# Shining_Pig.net
KiCad netlist of a schematic drawn in Altium Designer
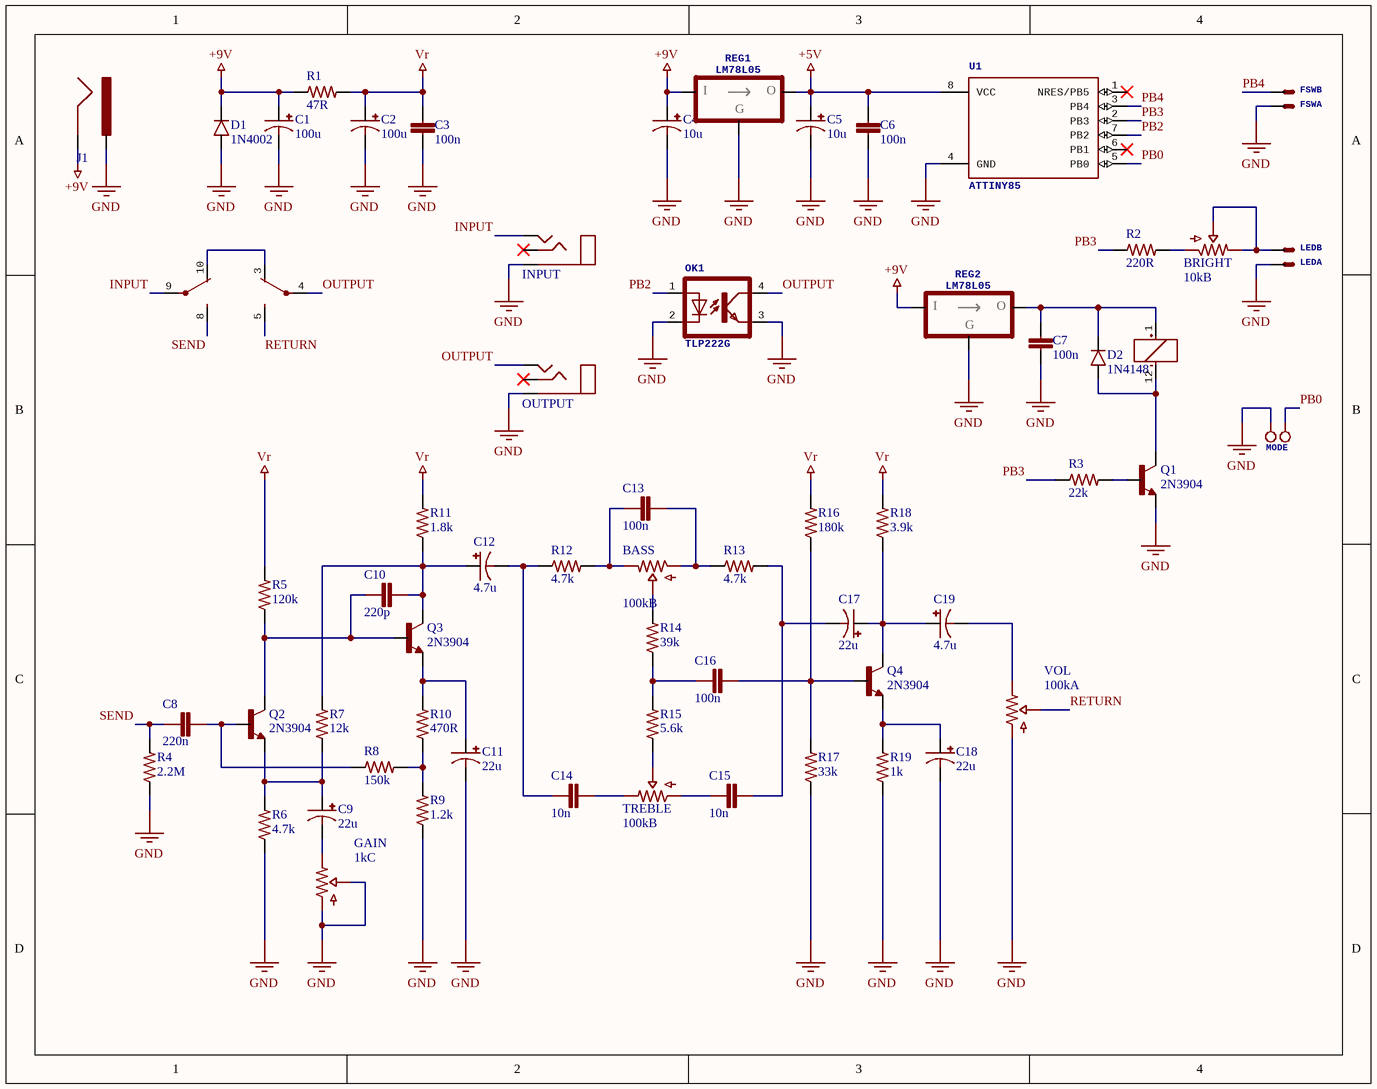
[diagram p0: Shining Pig.SchDoc]

(export (version "E")
  (design (tool "Eeschema 10.0.6"))
  (components
    (comp (ref "BASS")
      (value "100kB")
      (footprint "ALPHA_16mm_BOTTOM")
      (description "100k Lin potentiometer round shaft")
      (libsource (lib "Pedals") (part "POT_100kB_ALPHA_16mm"))
    )
    (comp (ref "BRIGHT")
      (value "10kB")
      (footprint "BOURNS_3362P")
      (description "10k Lin 3362P trimmer")
      (libsource (lib "Pedals") (part "TRIM_10kB_3362P"))
    )
    (comp (ref "C1")
      (value "100u")
      (footprint "ELEC_063_025")
      (description "100u 25V electrolytic capacitor")
      (libsource (lib "Pedals") (part "C_ELEC_100u_25V"))
    )
    (comp (ref "C2")
      (value "100u")
      (footprint "ELEC_063_025")
      (description "100u 25V electrolytic capacitor")
      (libsource (lib "Pedals") (part "C_ELEC_100u_25V"))
    )
    (comp (ref "C3")
      (value "100n")
      (footprint "CER_050")
      (description "100n MLCC X7R radial capacitor")
      (libsource (lib "Pedals") (part "C_CER_100n"))
    )
    (comp (ref "C4")
      (value "10u")
      (footprint "ELEC_040_020")
      (description "10u 50V electrolytic capacitor")
      (libsource (lib "Pedals") (part "C_ELEC_10u_50V"))
    )
    (comp (ref "C5")
      (value "10u")
      (footprint "ELEC_040_020")
      (description "10u 50V electrolytic capacitor")
      (libsource (lib "Pedals") (part "C_ELEC_10u_50V"))
    )
    (comp (ref "C6")
      (value "100n")
      (footprint "CER_050")
      (description "100n MLCC X7R radial capacitor")
      (libsource (lib "") (part "C_CER_100n_1"))
    )
    (comp (ref "C7")
      (value "100n")
      (footprint "CER_050")
      (description "100n MLCC X7R radial capacitor")
      (libsource (lib "Pedals") (part "C_CER_100n"))
    )
    (comp (ref "C8")
      (value "220n")
      (footprint "FILMBOX_SMALL")
      (description "220n 100V polyester film box capacitor")
      (libsource (lib "Pedals") (part "C_FILMBOX_220n"))
    )
    (comp (ref "C9")
      (value "22u")
      (footprint "ELEC_LESR_050_020")
      (description "22u 50V Low ESR ectrolytic capacitor")
      (libsource (lib "Pedals") (part "C_ELEC_LESR_22u_50V"))
    )
    (comp (ref "C10")
      (value "220p")
      (footprint "CER_050")
      (description "220p MLCC X7R radial capacitor")
      (libsource (lib "Pedals") (part "C_CER_220p"))
    )
    (comp (ref "C11")
      (value "22u")
      (footprint "ELEC_LESR_050_020")
      (description "22u 50V Low ESR ectrolytic capacitor")
      (libsource (lib "Pedals") (part "C_ELEC_LESR_22u_50V"))
    )
    (comp (ref "C12")
      (value "4.7u")
      (footprint "ELEC_LESR_050_020")
      (description "4.7u 50V Low ESR ectrolytic capacitor")
      (libsource (lib "Pedals") (part "C_ELEC_LESR_4.7u_50V"))
    )
    (comp (ref "C13")
      (value "100n")
      (footprint "FILMBOX_SMALL")
      (description "100n 100V polyester film box capacitor")
      (libsource (lib "Pedals") (part "C_FILMBOX_100n"))
    )
    (comp (ref "C14")
      (value "10n")
      (footprint "FILMBOX_SMALL")
      (description "10n 100V polyester film box capacitor")
      (libsource (lib "Pedals") (part "C_FILMBOX_10n"))
    )
    (comp (ref "C15")
      (value "10n")
      (footprint "FILMBOX_SMALL")
      (description "10n 100V polyester film box capacitor")
      (libsource (lib "Pedals") (part "C_FILMBOX_10n"))
    )
    (comp (ref "C16")
      (value "100n")
      (footprint "FILMBOX_SMALL")
      (description "100n 100V polyester film box capacitor")
      (libsource (lib "Pedals") (part "C_FILMBOX_100n"))
    )
    (comp (ref "C17")
      (value "22u")
      (footprint "ELEC_LESR_050_020")
      (description "22u 50V Low ESR ectrolytic capacitor")
      (libsource (lib "") (part "C_ELEC_LESR_22u_50V_1"))
    )
    (comp (ref "C18")
      (value "22u")
      (footprint "ELEC_LESR_050_020")
      (description "22u 50V Low ESR ectrolytic capacitor")
      (libsource (lib "Pedals") (part "C_ELEC_LESR_22u_50V"))
    )
    (comp (ref "C19")
      (value "4.7u")
      (footprint "ELEC_LESR_050_020")
      (description "4.7u 50V Low ESR ectrolytic capacitor")
      (libsource (lib "Pedals") (part "C_ELEC_LESR_4.7u_50V"))
    )
    (comp (ref "D1") (value "1N4002") (footprint "DO41_2") (libsource (lib "Pedals") (part "D_1N4002")))
    (comp (ref "D2") (value "1N4148") (footprint "DO35_2") (libsource (lib "Pedals") (part "D_1N4148")))
    (comp (ref "FSW")
      (value "J_JST-XH-02")
      (footprint "JST-XH-02")
      (description "2 Pins male XH header")
      (libsource (lib "Pedals") (part "J_JST-XH-02"))
    )
    (comp (ref "GAIN")
      (value "1kC")
      (footprint "ALPHA_16mm_BOTTOM")
      (description "1k Reverse log potentiometer round shaft")
      (libsource (lib "Pedals") (part "POT_1kC_ALPHA_16mm"))
    )
    (comp (ref "INPUT")
      (value "J_STEREO")
      (footprint "STEREO")
      (description "6.35mm stereo insulated socket jack PCB mounted")
      (libsource (lib "Pedals") (part "J_STEREO"))
    )
    (comp (ref "J1")
      (value "J_DC_JACK")
      (footprint "DC_JACK")
      (description "DC Power jack 2.1mm barrel")
      (libsource (lib "Pedals") (part "J_DC_JACK"))
    )
    (comp (ref "K1") (value "NA5W-K") (footprint "NA5") (libsource (lib "") (part "K_NA5W-K_2")))
    (comp (ref "LED")
      (value "J_JST-XH-02")
      (footprint "JST-XH-02")
      (description "2 Pins male XH header")
      (libsource (lib "Pedals") (part "J_JST-XH-02"))
    )
    (comp (ref "MODE")
      (value "J_HEADER_2PINS")
      (footprint "HEADER_2PINS")
      (description "2 Pins male header")
      (libsource (lib "Pedals") (part "J_HEADER_2PINS"))
    )
    (comp (ref "OK1") (value "TLP222G") (footprint "DIL4") (libsource (lib "Pedals") (part "OK_TLP222G")))
    (comp (ref "OUTPUT")
      (value "J_STEREO")
      (footprint "STEREO")
      (description "6.35mm stereo insulated socket jack PCB mounted")
      (libsource (lib "Pedals") (part "J_STEREO"))
    )
    (comp (ref "Q1") (value "2N3904") (footprint "TO92") (libsource (lib "Pedals") (part "Q_2N3904")))
    (comp (ref "Q2") (value "2N3904") (footprint "TO92") (libsource (lib "Pedals") (part "Q_2N3904")))
    (comp (ref "Q3") (value "2N3904") (footprint "TO92") (libsource (lib "Pedals") (part "Q_2N3904")))
    (comp (ref "Q4") (value "2N3904") (footprint "TO92") (libsource (lib "Pedals") (part "Q_2N3904")))
    (comp (ref "R1")
      (value "47R")
      (footprint "R_3_47R_025W")
      (description "47R metal film 1/4W Resistor")
      (libsource (lib "Pedals") (part "R_3_47R_025W"))
    )
    (comp (ref "R2")
      (value "220R")
      (footprint "R_3_220R_025W")
      (description "220R metal film 1/4W Resistor")
      (libsource (lib "Pedals") (part "R_3_220R_025W"))
    )
    (comp (ref "R3")
      (value "22k")
      (footprint "R_3_22k_025W")
      (description "22k metal film 1/4W Resistor")
      (libsource (lib "Pedals") (part "R_3_22k_025W"))
    )
    (comp (ref "R4")
      (value "2.2M")
      (footprint "R_3_2,2M_025W")
      (description "2.2M metal film 1/4W Resistor")
      (libsource (lib "Pedals") (part "R_3_2.2M_025W"))
    )
    (comp (ref "R5")
      (value "120k")
      (footprint "R_3_120k_025W")
      (description "120k metal film 1/4W Resistor")
      (libsource (lib "Pedals") (part "R_3_120k_025W"))
    )
    (comp (ref "R6")
      (value "4.7k")
      (footprint "R_3_4.7k_025W")
      (description "4.7kk metal film 1/4W Resistor")
      (libsource (lib "Pedals") (part "R_3_4.7k_025W"))
    )
    (comp (ref "R7")
      (value "12k")
      (footprint "R_3_12k_025W")
      (description "12k metal film 1/4W Resistor")
      (libsource (lib "Pedals") (part "R_3_12k_025W"))
    )
    (comp (ref "R8")
      (value "150k")
      (footprint "R_3_150k_025W")
      (description "150k metal film 1/4W Resistor")
      (libsource (lib "Pedals") (part "R_3_150k_025W"))
    )
    (comp (ref "R9")
      (value "1.2k")
      (footprint "R_3_1.2k_025W")
      (description "1.2k metal film 1/4W Resistor")
      (libsource (lib "Pedals") (part "R_3_1.2k_025W"))
    )
    (comp (ref "R10")
      (value "470R")
      (footprint "R_3_470R_025W")
      (description "470R metal film 1/4W Resistor")
      (libsource (lib "Pedals") (part "R_3_470R_025W"))
    )
    (comp (ref "R11")
      (value "1.8k")
      (footprint "R_3_1.8k_025W")
      (description "1.8k metal film 1/4W Resistor")
      (libsource (lib "Pedals") (part "R_3_1.8k_025W"))
    )
    (comp (ref "R12")
      (value "4.7k")
      (footprint "R_3_4.7k_025W")
      (description "4.7kk metal film 1/4W Resistor")
      (libsource (lib "Pedals") (part "R_3_4.7k_025W"))
    )
    (comp (ref "R13")
      (value "4.7k")
      (footprint "R_3_4.7k_025W")
      (description "4.7kk metal film 1/4W Resistor")
      (libsource (lib "Pedals") (part "R_3_4.7k_025W"))
    )
    (comp (ref "R14")
      (value "39k")
      (footprint "R_3_39k_025W")
      (description "39k metal film 1/4W Resistor")
      (libsource (lib "Pedals") (part "R_3_39k_025W"))
    )
    (comp (ref "R15")
      (value "5.6k")
      (footprint "R_3_5.6k_025W")
      (description "5.6k metal film 1/4W Resistor")
      (libsource (lib "Pedals") (part "R_3_5.6k_025W"))
    )
    (comp (ref "R16")
      (value "180k")
      (footprint "R_3_180k_025W")
      (description "180k metal film 1/4W Resistor")
      (libsource (lib "Pedals") (part "R_3_180k_025W"))
    )
    (comp (ref "R17")
      (value "33k")
      (footprint "R_3_33k_025W")
      (description "33k metal film 1/4W Resistor")
      (libsource (lib "Pedals") (part "R_3_33k_025W"))
    )
    (comp (ref "R18")
      (value "3.9k")
      (footprint "R_3_3.9k_025W")
      (description "3.9k metal film 1/4W Resistor")
      (libsource (lib "Pedals") (part "R_3_3.9k_025W"))
    )
    (comp (ref "R19")
      (value "1k")
      (footprint "R_3_1k_025W")
      (description "1k metal film 1/4W Resistor")
      (libsource (lib "Pedals") (part "R_3_1k_025W"))
    )
    (comp (ref "REG1")
      (value "LM78L05")
      (footprint "TO92")
      (description "78L05")
      (libsource (lib "Pedals") (part "REG_LM78L05"))
    )
    (comp (ref "REG2")
      (value "LM78L05")
      (footprint "TO92")
      (description "78L05")
      (libsource (lib "Pedals") (part "REG_LM78L05"))
    )
    (comp (ref "TREBLE")
      (value "100kB")
      (footprint "ALPHA_16mm_BOTTOM")
      (description "100k Lin potentiometer round shaft")
      (libsource (lib "Pedals") (part "POT_100kB_ALPHA_16mm"))
    )
    (comp (ref "U1")
      (value "ATTINY85")
      (footprint "DIP8")
      (description "ATTINY85-20PU")
      (libsource (lib "Pedals") (part "U_ATTINY85"))
    )
    (comp (ref "VOL")
      (value "100kA")
      (footprint "ALPHA_16mm_BOTTOM")
      (description "100k Log potentiometer round shaft")
      (libsource (lib "Pedals") (part "POT_100kA_ALPHA_16mm"))
    )
  )
  (nets
    (net (code "1") (name "+5V") (class "Default")
      (node (ref "C5") (pin "+") (pinfunction "+_+") (pintype "passive"))
      (node (ref "C6") (pin "2") (pinfunction "2_2") (pintype "passive"))
      (node (ref "REG1") (pin "3") (pinfunction "VO_3") (pintype "power_in"))
      (node (ref "U1") (pin "8") (pinfunction "VCC_8") (pintype "power_in"))
    )
    (net (code "2") (name "+9V") (class "Default")
      (node (ref "C1") (pin "+") (pinfunction "+_+") (pintype "passive"))
      (node (ref "C4") (pin "+") (pinfunction "+_+") (pintype "passive"))
      (node (ref "D1") (pin "C") (pinfunction "C_C") (pintype "passive"))
      (node (ref "J1") (pin "GND") (pinfunction "GND_GND") (pintype "passive"))
      (node (ref "R1") (pin "1") (pinfunction "1_1") (pintype "passive"))
      (node (ref "REG1") (pin "1") (pinfunction "VI_1") (pintype "power_in"))
      (node (ref "REG2") (pin "1") (pinfunction "VI_1") (pintype "power_in"))
    )
    (net (code "3") (name "/INPUT") (class "Default")
      (node (ref "INPUT") (pin "T") (pinfunction "T_T") (pintype "passive"))
      (node (ref "K1") (pin "9") (pinfunction "P_9") (pintype "passive"))
    )
    (net (code "4") (name "/OUTPUT") (class "Default")
      (node (ref "K1") (pin "4") (pinfunction "P_4") (pintype "passive"))
      (node (ref "OK1") (pin "4") (pinfunction "COL_4") (pintype "passive"))
      (node (ref "OUTPUT") (pin "T") (pinfunction "T_T") (pintype "passive"))
    )
    (net (code "5") (name "/PB0") (class "Default")
      (node (ref "MODE") (pin "2") (pinfunction "2_2") (pintype "passive"))
      (node (ref "U1") (pin "5") (pinfunction "PB0_5") (pintype "bidirectional"))
    )
    (net (code "6") (name "/PB2") (class "Default")
      (node (ref "OK1") (pin "1") (pinfunction "A_1") (pintype "passive"))
      (node (ref "U1") (pin "7") (pinfunction "PB2_7") (pintype "bidirectional"))
    )
    (net (code "7") (name "/PB3") (class "Default")
      (node (ref "R2") (pin "1") (pinfunction "1_1") (pintype "passive"))
      (node (ref "R3") (pin "1") (pinfunction "1_1") (pintype "passive"))
      (node (ref "U1") (pin "2") (pinfunction "PB3_2") (pintype "bidirectional"))
    )
    (net (code "8") (name "/PB4") (class "Default")
      (node (ref "FSW") (pin "1") (pinfunction "S_1") (pintype "passive"))
      (node (ref "U1") (pin "3") (pinfunction "PB4_3") (pintype "bidirectional"))
    )
    (net (code "9") (name "/RETURN") (class "Default")
      (node (ref "K1") (pin "5") (pinfunction "S_5") (pintype "passive"))
      (node (ref "VOL") (pin "2") (pinfunction "2_2") (pintype "passive"))
    )
    (net (code "10") (name "/SEND") (class "Default")
      (node (ref "C8") (pin "2") (pinfunction "2_2") (pintype "passive"))
      (node (ref "K1") (pin "8") (pinfunction "S_8") (pintype "passive"))
      (node (ref "R4") (pin "2") (pinfunction "2_2") (pintype "passive"))
    )
    (net (code "11") (name "GND") (class "Default")
      (node (ref "C1") (pin "-") (pinfunction "-_-") (pintype "passive"))
      (node (ref "C11") (pin "-") (pinfunction "-_-") (pintype "passive"))
      (node (ref "C18") (pin "-") (pinfunction "-_-") (pintype "passive"))
      (node (ref "C2") (pin "-") (pinfunction "-_-") (pintype "passive"))
      (node (ref "C3") (pin "2") (pinfunction "2_2") (pintype "passive"))
      (node (ref "C4") (pin "-") (pinfunction "-_-") (pintype "passive"))
      (node (ref "C5") (pin "-") (pinfunction "-_-") (pintype "passive"))
      (node (ref "C6") (pin "1") (pinfunction "1_1") (pintype "passive"))
      (node (ref "C7") (pin "2") (pinfunction "2_2") (pintype "passive"))
      (node (ref "D1") (pin "A") (pinfunction "A_A") (pintype "passive"))
      (node (ref "FSW") (pin "2") (pinfunction "S_2") (pintype "passive"))
      (node (ref "GAIN") (pin "1") (pinfunction "1_1") (pintype "passive"))
      (node (ref "GAIN") (pin "2") (pinfunction "2_2") (pintype "passive"))
      (node (ref "INPUT") (pin "S") (pinfunction "S_S") (pintype "passive"))
      (node (ref "J1") (pin "PWR") (pinfunction "PWR_PWR") (pintype "passive"))
      (node (ref "LED") (pin "2") (pinfunction "S_2") (pintype "passive"))
      (node (ref "MODE") (pin "1") (pinfunction "1_1") (pintype "passive"))
      (node (ref "OK1") (pin "2") (pinfunction "C_2") (pintype "passive"))
      (node (ref "OK1") (pin "3") (pinfunction "EMIT_3") (pintype "passive"))
      (node (ref "OUTPUT") (pin "S") (pinfunction "S_S") (pintype "passive"))
      (node (ref "Q1") (pin "3") (pinfunction "E_3") (pintype "passive"))
      (node (ref "R17") (pin "1") (pinfunction "1_1") (pintype "passive"))
      (node (ref "R19") (pin "1") (pinfunction "1_1") (pintype "passive"))
      (node (ref "R4") (pin "1") (pinfunction "1_1") (pintype "passive"))
      (node (ref "R6") (pin "1") (pinfunction "1_1") (pintype "passive"))
      (node (ref "R9") (pin "1") (pinfunction "1_1") (pintype "passive"))
      (node (ref "REG1") (pin "2") (pinfunction "GND_2") (pintype "power_in"))
      (node (ref "REG2") (pin "2") (pinfunction "GND_2") (pintype "power_in"))
      (node (ref "U1") (pin "4") (pinfunction "GND_4") (pintype "power_in"))
      (node (ref "VOL") (pin "1") (pinfunction "1_1") (pintype "passive"))
    )
    (net (code "12") (name "Net-(BASS-Pad1)") (class "Default")
      (node (ref "BASS") (pin "1") (pinfunction "1_1") (pintype "passive"))
      (node (ref "C13") (pin "1") (pinfunction "1_1") (pintype "passive"))
      (node (ref "R13") (pin "1") (pinfunction "1_1") (pintype "passive"))
    )
    (net (code "13") (name "Net-(BASS-Pad2)") (class "Default")
      (node (ref "BASS") (pin "2") (pinfunction "2_2") (pintype "passive"))
      (node (ref "R14") (pin "2") (pinfunction "2_2") (pintype "passive"))
    )
    (net (code "14") (name "Net-(BASS-Pad3)") (class "Default")
      (node (ref "BASS") (pin "3") (pinfunction "3_3") (pintype "passive"))
      (node (ref "C13") (pin "2") (pinfunction "2_2") (pintype "passive"))
      (node (ref "R12") (pin "2") (pinfunction "2_2") (pintype "passive"))
    )
    (net (code "15") (name "Net-(BRIGHT-Pad1)") (class "Default")
      (node (ref "BRIGHT") (pin "1") (pinfunction "1_1") (pintype "passive"))
      (node (ref "R2") (pin "2") (pinfunction "2_2") (pintype "passive"))
    )
    (net (code "16") (name "Net-(C9-Pad-)") (class "Default")
      (node (ref "C9") (pin "-") (pinfunction "-_-") (pintype "passive"))
      (node (ref "GAIN") (pin "3") (pinfunction "3_3") (pintype "passive"))
    )
    (net (code "17") (name "Net-(C12-Pad-)") (class "Default")
      (node (ref "C12") (pin "-") (pinfunction "-_-") (pintype "passive"))
      (node (ref "C14") (pin "2") (pinfunction "2_2") (pintype "passive"))
      (node (ref "R12") (pin "1") (pinfunction "1_1") (pintype "passive"))
    )
    (net (code "18") (name "Net-(C14-Pad1)") (class "Default")
      (node (ref "C14") (pin "1") (pinfunction "1_1") (pintype "passive"))
      (node (ref "TREBLE") (pin "3") (pinfunction "3_3") (pintype "passive"))
    )
    (net (code "19") (name "Net-(C15-Pad1)") (class "Default")
      (node (ref "C15") (pin "1") (pinfunction "1_1") (pintype "passive"))
      (node (ref "C17") (pin "-") (pinfunction "-_-") (pintype "passive"))
      (node (ref "R13") (pin "2") (pinfunction "2_2") (pintype "passive"))
    )
    (net (code "20") (name "Net-(C15-Pad2)") (class "Default")
      (node (ref "C15") (pin "2") (pinfunction "2_2") (pintype "passive"))
      (node (ref "TREBLE") (pin "1") (pinfunction "1_1") (pintype "passive"))
    )
    (net (code "21") (name "Net-(C16-Pad2)") (class "Default")
      (node (ref "C16") (pin "2") (pinfunction "2_2") (pintype "passive"))
      (node (ref "R14") (pin "1") (pinfunction "1_1") (pintype "passive"))
      (node (ref "R15") (pin "2") (pinfunction "2_2") (pintype "passive"))
    )
    (net (code "22") (name "Net-(C19-Pad-)") (class "Default")
      (node (ref "C19") (pin "-") (pinfunction "-_-") (pintype "passive"))
      (node (ref "VOL") (pin "3") (pinfunction "3_3") (pintype "passive"))
    )
    (net (code "23") (name "Net-(K1A-+)") (class "Default")
      (node (ref "C7") (pin "1") (pinfunction "1_1") (pintype "passive"))
      (node (ref "D2") (pin "C") (pinfunction "C_C") (pintype "passive"))
      (node (ref "K1") (pin "1") (pinfunction "+_1") (pintype "passive"))
      (node (ref "REG2") (pin "3") (pinfunction "VO_3") (pintype "power_in"))
    )
    (net (code "24") (name "Net-(K1A--)") (class "Default")
      (node (ref "D2") (pin "A") (pinfunction "A_A") (pintype "passive"))
      (node (ref "K1") (pin "12") (pinfunction "-_12") (pintype "passive"))
      (node (ref "Q1") (pin "1") (pinfunction "C_1") (pintype "passive"))
    )
    (net (code "25") (name "Net-(K1B-O)") (class "Default")
      (node (ref "K1") (pin "10") (pinfunction "O_10") (pintype "passive"))
      (node (ref "K1") (pin "3") (pinfunction "O_3") (pintype "passive"))
    )
    (net (code "26") (name "Net-(LEDB-S)") (class "Default")
      (node (ref "BRIGHT") (pin "2") (pinfunction "2_2") (pintype "passive"))
      (node (ref "BRIGHT") (pin "3") (pinfunction "3_3") (pintype "passive"))
      (node (ref "LED") (pin "1") (pinfunction "S_1") (pintype "passive"))
    )
    (net (code "27") (name "Net-(Q1-B)") (class "Default")
      (node (ref "Q1") (pin "2") (pinfunction "B_2") (pintype "passive"))
      (node (ref "R3") (pin "2") (pinfunction "2_2") (pintype "passive"))
    )
    (net (code "28") (name "Net-(Q2-B)") (class "Default")
      (node (ref "C8") (pin "1") (pinfunction "1_1") (pintype "passive"))
      (node (ref "Q2") (pin "2") (pinfunction "B_2") (pintype "passive"))
      (node (ref "R8") (pin "1") (pinfunction "1_1") (pintype "passive"))
    )
    (net (code "29") (name "Net-(Q2-C)") (class "Default")
      (node (ref "C10") (pin "2") (pinfunction "2_2") (pintype "passive"))
      (node (ref "Q2") (pin "1") (pinfunction "C_1") (pintype "passive"))
      (node (ref "Q3") (pin "2") (pinfunction "B_2") (pintype "passive"))
      (node (ref "R5") (pin "1") (pinfunction "1_1") (pintype "passive"))
    )
    (net (code "30") (name "Net-(Q2-E)") (class "Default")
      (node (ref "C9") (pin "+") (pinfunction "+_+") (pintype "passive"))
      (node (ref "Q2") (pin "3") (pinfunction "E_3") (pintype "passive"))
      (node (ref "R6") (pin "2") (pinfunction "2_2") (pintype "passive"))
      (node (ref "R7") (pin "1") (pinfunction "1_1") (pintype "passive"))
    )
    (net (code "31") (name "Net-(Q3-C)") (class "Default")
      (node (ref "C10") (pin "1") (pinfunction "1_1") (pintype "passive"))
      (node (ref "C12") (pin "+") (pinfunction "+_+") (pintype "passive"))
      (node (ref "Q3") (pin "1") (pinfunction "C_1") (pintype "passive"))
      (node (ref "R11") (pin "1") (pinfunction "1_1") (pintype "passive"))
      (node (ref "R7") (pin "2") (pinfunction "2_2") (pintype "passive"))
    )
    (net (code "32") (name "Net-(Q3-E)") (class "Default")
      (node (ref "C11") (pin "+") (pinfunction "+_+") (pintype "passive"))
      (node (ref "Q3") (pin "3") (pinfunction "E_3") (pintype "passive"))
      (node (ref "R10") (pin "2") (pinfunction "2_2") (pintype "passive"))
    )
    (net (code "33") (name "Net-(Q4-B)") (class "Default")
      (node (ref "C16") (pin "1") (pinfunction "1_1") (pintype "passive"))
      (node (ref "Q4") (pin "2") (pinfunction "B_2") (pintype "passive"))
      (node (ref "R16") (pin "1") (pinfunction "1_1") (pintype "passive"))
      (node (ref "R17") (pin "2") (pinfunction "2_2") (pintype "passive"))
    )
    (net (code "34") (name "Net-(Q4-C)") (class "Default")
      (node (ref "C17") (pin "+") (pinfunction "+_+") (pintype "passive"))
      (node (ref "C19") (pin "+") (pinfunction "+_+") (pintype "passive"))
      (node (ref "Q4") (pin "1") (pinfunction "C_1") (pintype "passive"))
      (node (ref "R18") (pin "1") (pinfunction "1_1") (pintype "passive"))
    )
    (net (code "35") (name "Net-(Q4-E)") (class "Default")
      (node (ref "C18") (pin "+") (pinfunction "+_+") (pintype "passive"))
      (node (ref "Q4") (pin "3") (pinfunction "E_3") (pintype "passive"))
      (node (ref "R19") (pin "2") (pinfunction "2_2") (pintype "passive"))
    )
    (net (code "36") (name "Net-(R10-Pad1)") (class "Default")
      (node (ref "R10") (pin "1") (pinfunction "1_1") (pintype "passive"))
      (node (ref "R8") (pin "2") (pinfunction "2_2") (pintype "passive"))
      (node (ref "R9") (pin "2") (pinfunction "2_2") (pintype "passive"))
    )
    (net (code "37") (name "Net-(R15-Pad1)") (class "Default")
      (node (ref "R15") (pin "1") (pinfunction "1_1") (pintype "passive"))
      (node (ref "TREBLE") (pin "2") (pinfunction "2_2") (pintype "passive"))
    )
    (net (code "38") (name "Vr") (class "Default")
      (node (ref "C2") (pin "+") (pinfunction "+_+") (pintype "passive"))
      (node (ref "C3") (pin "1") (pinfunction "1_1") (pintype "passive"))
      (node (ref "R1") (pin "2") (pinfunction "2_2") (pintype "passive"))
      (node (ref "R11") (pin "2") (pinfunction "2_2") (pintype "passive"))
      (node (ref "R16") (pin "2") (pinfunction "2_2") (pintype "passive"))
      (node (ref "R18") (pin "2") (pinfunction "2_2") (pintype "passive"))
      (node (ref "R5") (pin "2") (pinfunction "2_2") (pintype "passive"))
    )
    (net (code "39") (name "unconnected-(INPUT-PadR)") (class "Default")
      (node (ref "INPUT") (pin "R") (pinfunction "R_R") (pintype "passive+no_connect"))
    )
    (net (code "40") (name "unconnected-(OUTPUT-PadR)") (class "Default")
      (node (ref "OUTPUT") (pin "R") (pinfunction "R_R") (pintype "passive+no_connect"))
    )
    (net (code "41") (name "unconnected-(U1-NRES{slash}PB5-Pad1)") (class "Default")
      (node (ref "U1") (pin "1") (pinfunction "NRES/PB5_1") (pintype "bidirectional+no_connect"))
    )
    (net (code "42") (name "unconnected-(U1-PB1-Pad6)") (class "Default")
      (node (ref "U1") (pin "6") (pinfunction "PB1_6") (pintype "bidirectional+no_connect"))
    )
  )
)
